# gatedriver_ixys.net
KiCad netlist of a schematic drawn in EAGLE
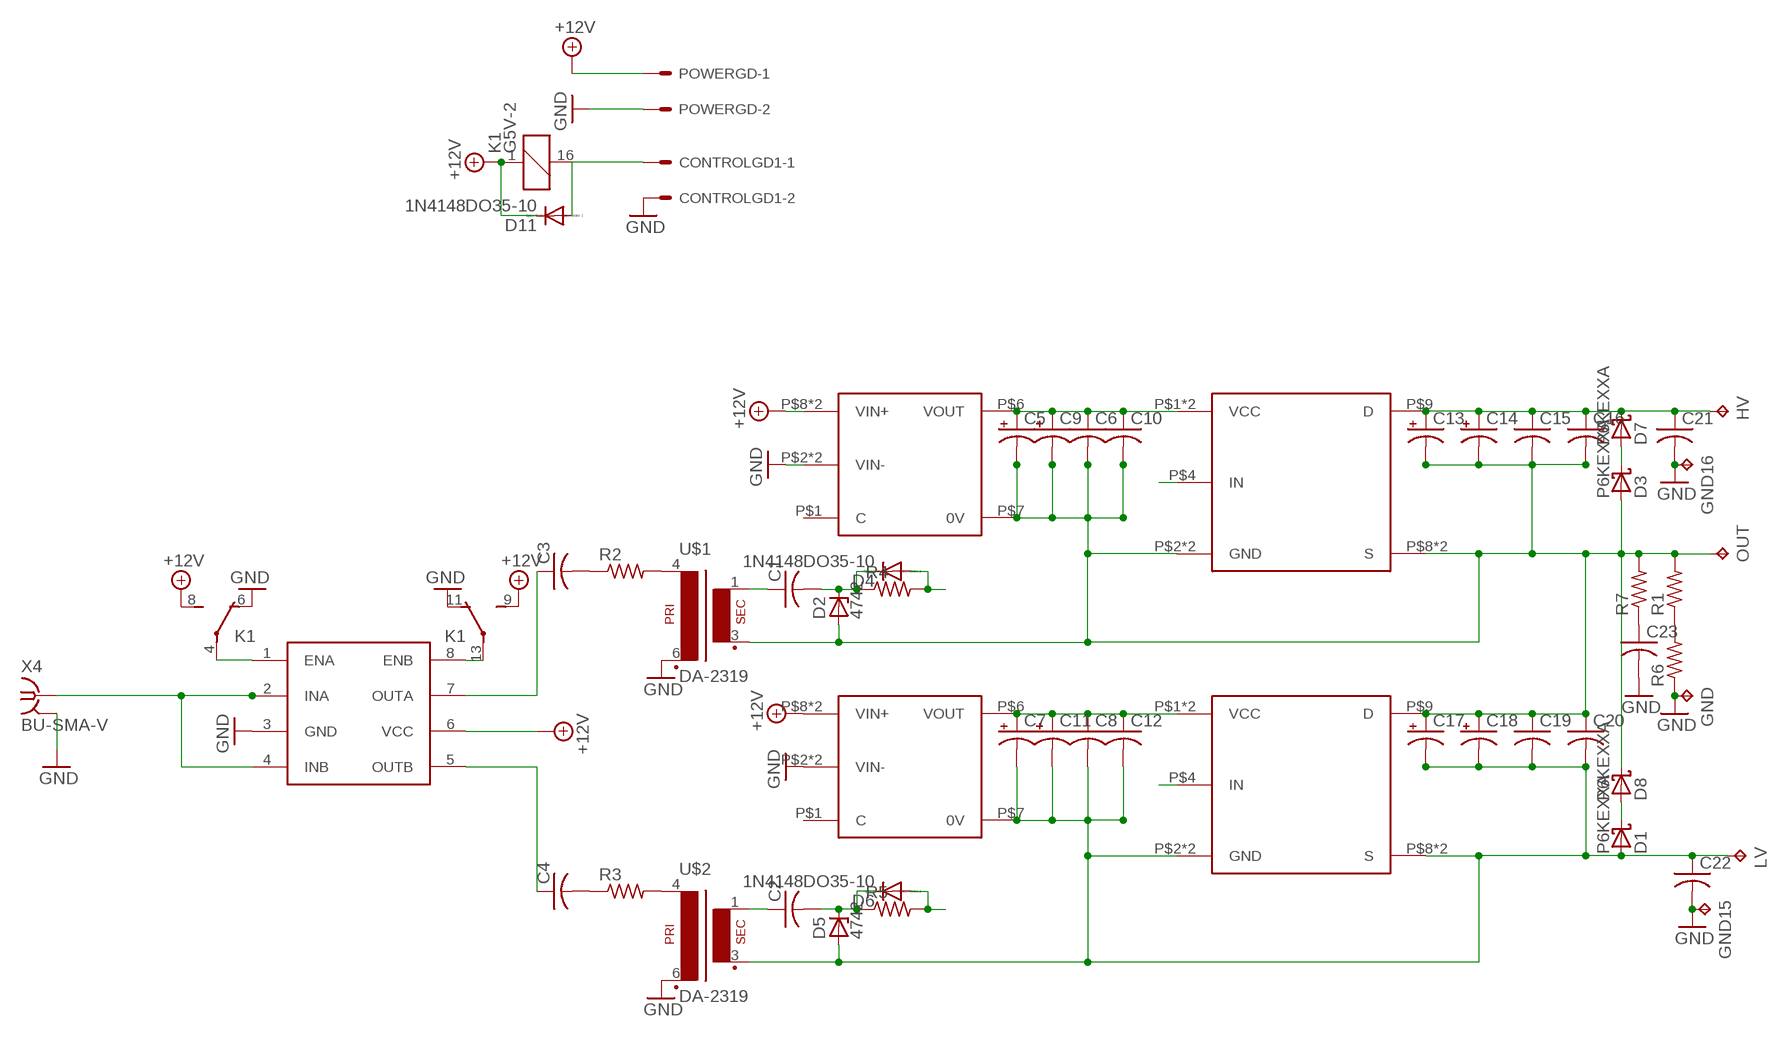
[diagram p0: schematic, sheet 1]

(export (version "E")
  (design (tool "Eeschema 10.0.6"))
  (components
    (comp (ref "C1")
      (value "C-US050-055X075")
      (footprint "eagle-import:C050-055X075")
      (libsource (lib "eagle-import") (part "resistor_C-US050-055X075"))
    )
    (comp (ref "C2")
      (value "C-US050-055X075")
      (footprint "eagle-import:C050-055X075")
      (libsource (lib "eagle-import") (part "resistor_C-US050-055X075"))
    )
    (comp (ref "C3")
      (value "C-US050-055X075")
      (footprint "eagle-import:C050-055X075")
      (libsource (lib "eagle-import") (part "resistor_C-US050-055X075"))
    )
    (comp (ref "C4")
      (value "C-US050-055X075")
      (footprint "eagle-import:C050-055X075")
      (libsource (lib "eagle-import") (part "resistor_C-US050-055X075"))
    )
    (comp (ref "C5")
      (value "CPOL-USE5-10.5")
      (footprint "eagle-import:E5-10,5")
      (libsource (lib "eagle-import") (part "CPOL-USE5-10.5"))
    )
    (comp (ref "C6")
      (value "C-US050-075X075")
      (footprint "eagle-import:C050-075X075")
      (libsource (lib "eagle-import") (part "resistor_C-US050-075X075"))
    )
    (comp (ref "C7")
      (value "CPOL-USE5-10.5")
      (footprint "eagle-import:E5-10,5")
      (libsource (lib "eagle-import") (part "CPOL-USE5-10.5"))
    )
    (comp (ref "C8")
      (value "C-US050-075X075")
      (footprint "eagle-import:C050-075X075")
      (libsource (lib "eagle-import") (part "resistor_C-US050-075X075"))
    )
    (comp (ref "C9")
      (value "CPOL-USE5-10.5")
      (footprint "eagle-import:E5-10,5")
      (libsource (lib "eagle-import") (part "CPOL-USE5-10.5"))
    )
    (comp (ref "C10")
      (value "C-US050-075X075")
      (footprint "eagle-import:C050-075X075")
      (libsource (lib "eagle-import") (part "resistor_C-US050-075X075"))
    )
    (comp (ref "C11")
      (value "CPOL-USE5-10.5")
      (footprint "eagle-import:E5-10,5")
      (libsource (lib "eagle-import") (part "CPOL-USE5-10.5"))
    )
    (comp (ref "C12")
      (value "C-US050-075X075")
      (footprint "eagle-import:C050-075X075")
      (libsource (lib "eagle-import") (part "resistor_C-US050-075X075"))
    )
    (comp (ref "C13")
      (value "CPOL-USE5-10.5")
      (footprint "eagle-import:E5-10,5")
      (libsource (lib "eagle-import") (part "CPOL-USE5-10.5"))
    )
    (comp (ref "C14")
      (value "CPOL-USE5-10.5")
      (footprint "eagle-import:E5-10,5")
      (libsource (lib "eagle-import") (part "CPOL-USE5-10.5"))
    )
    (comp (ref "C15")
      (value "C-US050-075X075")
      (footprint "eagle-import:C050-075X075")
      (libsource (lib "eagle-import") (part "resistor_C-US050-075X075"))
    )
    (comp (ref "C16")
      (value "C-US050-075X075")
      (footprint "eagle-import:C050-075X075")
      (libsource (lib "eagle-import") (part "resistor_C-US050-075X075"))
    )
    (comp (ref "C17")
      (value "CPOL-USE5-10.5")
      (footprint "eagle-import:E5-10,5")
      (libsource (lib "eagle-import") (part "CPOL-USE5-10.5"))
    )
    (comp (ref "C18")
      (value "CPOL-USE5-10.5")
      (footprint "eagle-import:E5-10,5")
      (libsource (lib "eagle-import") (part "CPOL-USE5-10.5"))
    )
    (comp (ref "C19")
      (value "C-US050-075X075")
      (footprint "eagle-import:C050-075X075")
      (libsource (lib "eagle-import") (part "resistor_C-US050-075X075"))
    )
    (comp (ref "C20")
      (value "C-US050-075X075")
      (footprint "eagle-import:C050-075X075")
      (libsource (lib "eagle-import") (part "resistor_C-US050-075X075"))
    )
    (comp (ref "C21")
      (value "C-US102-064X133")
      (footprint "eagle-import:C102-064X133")
      (libsource (lib "eagle-import") (part "C-US102-064X133"))
    )
    (comp (ref "C22")
      (value "C-US102-064X133")
      (footprint "eagle-import:C102-064X133")
      (libsource (lib "eagle-import") (part "C-US102-064X133"))
    )
    (comp (ref "C23")
      (value "C-US102-064X133")
      (footprint "eagle-import:C102-064X133")
      (libsource (lib "eagle-import") (part "C-US102-064X133"))
    )
    (comp (ref "CONTROLGD1")
      (value "KK-156-2")
      (footprint "eagle-import:KK-156-2")
      (libsource (lib "eagle-import") (part "KK-156-2"))
    )
    (comp (ref "D1")
      (value "P6KEXXA")
      (footprint "eagle-import:C1702-15")
      (libsource (lib "eagle-import") (part "P6KEXXA"))
    )
    (comp (ref "D2")
      (value "4742")
      (footprint "eagle-import:ZDIO-10")
      (libsource (lib "eagle-import") (part "ZENER-DIODEZD-10"))
    )
    (comp (ref "D3")
      (value "P6KEXXA")
      (footprint "eagle-import:C1702-15")
      (libsource (lib "eagle-import") (part "P6KEXXA"))
    )
    (comp (ref "D4")
      (value "1N4148DO35-10")
      (footprint "eagle-import:DO35-10")
      (libsource (lib "eagle-import") (part "1N4148DO35-10"))
    )
    (comp (ref "D5")
      (value "4742")
      (footprint "eagle-import:ZDIO-10")
      (libsource (lib "eagle-import") (part "ZENER-DIODEZD-10"))
    )
    (comp (ref "D6")
      (value "1N4148DO35-10")
      (footprint "eagle-import:DO35-10")
      (libsource (lib "eagle-import") (part "1N4148DO35-10"))
    )
    (comp (ref "D7")
      (value "P6KEXXA")
      (footprint "eagle-import:C1702-15")
      (libsource (lib "eagle-import") (part "P6KEXXA"))
    )
    (comp (ref "D8")
      (value "P6KEXXA")
      (footprint "eagle-import:C1702-15")
      (libsource (lib "eagle-import") (part "P6KEXXA"))
    )
    (comp (ref "D11")
      (value "1N4148DO35-10")
      (footprint "eagle-import:DO35-10")
      (libsource (lib "eagle-import") (part "1N4148DO35-10"))
    )
    (comp (ref "DC1")
      (value "NCS")
      (footprint "eagle-import:NCS")
      (libsource (lib "eagle-import") (part "NCS"))
    )
    (comp (ref "DC2")
      (value "NCS")
      (footprint "eagle-import:NCS")
      (libsource (lib "eagle-import") (part "NCS"))
    )
    (comp (ref "GND")
      (value "TPPAD1-20Y")
      (footprint "eagle-import:P1-20Y")
      (libsource (lib "eagle-import") (part "TPPAD1-20Y"))
    )
    (comp (ref "GND15")
      (value "TPPAD1-20Y")
      (footprint "eagle-import:P1-20Y")
      (libsource (lib "eagle-import") (part "TPPAD1-20Y"))
    )
    (comp (ref "GND16")
      (value "TPPAD1-20Y")
      (footprint "eagle-import:P1-20Y")
      (libsource (lib "eagle-import") (part "TPPAD1-20Y"))
    )
    (comp (ref "HV")
      (value "TPPAD1-20Y")
      (footprint "eagle-import:P1-20Y")
      (libsource (lib "eagle-import") (part "TPPAD1-20Y"))
    )
    (comp (ref "K1")
      (value "G5V-2")
      (footprint "eagle-import:G5V-2")
      (fields (field (name "MPN") "G5V-2 5DC"))
      (libsource (lib "eagle-import") (part "G5V-2"))
    )
    (comp (ref "LV")
      (value "TPPAD1-20Y")
      (footprint "eagle-import:P1-20Y")
      (libsource (lib "eagle-import") (part "TPPAD1-20Y"))
    )
    (comp (ref "OUT")
      (value "TPPAD1-20Y")
      (footprint "eagle-import:P1-20Y")
      (libsource (lib "eagle-import") (part "TPPAD1-20Y"))
    )
    (comp (ref "POWERGD")
      (value "KK-156-2")
      (footprint "eagle-import:KK-156-2")
      (libsource (lib "eagle-import") (part "KK-156-2"))
    )
    (comp (ref "R1")
      (value "R-US_0414/15")
      (footprint "eagle-import:0414_15")
      (libsource (lib "eagle-import") (part "R-US_0414/15"))
    )
    (comp (ref "R2")
      (value "R-US_0207/15")
      (footprint "eagle-import:0207_15")
      (libsource (lib "eagle-import") (part "R-US_0207/15"))
    )
    (comp (ref "R3")
      (value "R-US_0207/12")
      (footprint "eagle-import:0207_12")
      (libsource (lib "eagle-import") (part "R-US_0207/12"))
    )
    (comp (ref "R4")
      (value "R-US_0207/10")
      (footprint "eagle-import:0207_10")
      (libsource (lib "eagle-import") (part "R-US_0207/10"))
    )
    (comp (ref "R5")
      (value "R-US_0207/10")
      (footprint "eagle-import:0207_10")
      (libsource (lib "eagle-import") (part "R-US_0207/10"))
    )
    (comp (ref "R6")
      (value "R-US_0414/15")
      (footprint "eagle-import:0414_15")
      (libsource (lib "eagle-import") (part "R-US_0414/15"))
    )
    (comp (ref "R7")
      (value "R-US_0414/15")
      (footprint "eagle-import:0414_15")
      (libsource (lib "eagle-import") (part "R-US_0414/15"))
    )
    (comp (ref "U$1")
      (value "DA-2319")
      (footprint "eagle-import:DIL06")
      (libsource (lib "eagle-import") (part "DA-2319"))
    )
    (comp (ref "U$2")
      (value "DA-2319")
      (footprint "eagle-import:DIL06")
      (libsource (lib "eagle-import") (part "DA-2319"))
    )
    (comp (ref "U$3")
      (value "UCC27425")
      (footprint "eagle-import:DIL08")
      (libsource (lib "eagle-import") (part "UCC27425"))
    )
    (comp (ref "U$8")
      (value "IXZ631DF12N100")
      (footprint "eagle-import:IXZ631DF12N100")
      (libsource (lib "eagle-import") (part "IXZ631DF12N100"))
    )
    (comp (ref "U$9")
      (value "IXZ631DF12N100")
      (footprint "eagle-import:IXZ631DF12N100")
      (libsource (lib "eagle-import") (part "IXZ631DF12N100"))
    )
    (comp (ref "X4")
      (value "BU-SMA-V")
      (footprint "eagle-import:BU-SMA-V")
      (libsource (lib "eagle-import") (part "BU-SMA-V"))
    )
  )
  (nets
    (net (code "1") (name "+12V") (class "Default")
      (node (ref "D11") (pin "C") (pinfunction "C_C") (pintype "passive"))
      (node (ref "DC1") (pin "P$8") (pinfunction "VIN+_P$8") (pintype "bidirectional"))
      (node (ref "DC1") (pin "P$9") (pinfunction "VIN+_P$9") (pintype "bidirectional"))
      (node (ref "DC2") (pin "P$8") (pinfunction "VIN+_P$8") (pintype "bidirectional"))
      (node (ref "DC2") (pin "P$9") (pinfunction "VIN+_P$9") (pintype "bidirectional"))
      (node (ref "K1") (pin "1") (pinfunction "1_1") (pintype "passive"))
      (node (ref "K1") (pin "8") (pinfunction "S_8") (pintype "passive"))
      (node (ref "K1") (pin "9") (pinfunction "S_9") (pintype "passive"))
      (node (ref "POWERGD") (pin "1") (pinfunction "S_1") (pintype "passive"))
      (node (ref "U$3") (pin "6") (pinfunction "VCC_6") (pintype "bidirectional"))
    )
    (net (code "2") (name "/GD_HI") (class "Default")
      (node (ref "D4") (pin "A") (pinfunction "A_A") (pintype "passive"))
      (node (ref "R4") (pin "2") (pinfunction "2_2") (pintype "passive"))
      (node (ref "U$8") (pin "P$4") (pinfunction "IN_P$4") (pintype "bidirectional"))
    )
    (net (code "3") (name "/GD_LO") (class "Default")
      (node (ref "D6") (pin "A") (pinfunction "A_A") (pintype "passive"))
      (node (ref "R5") (pin "2") (pinfunction "2_2") (pintype "passive"))
      (node (ref "U$9") (pin "P$4") (pinfunction "IN_P$4") (pintype "bidirectional"))
    )
    (net (code "4") (name "GND") (class "Default")
      (node (ref "C21") (pin "2") (pinfunction "2_2") (pintype "passive"))
      (node (ref "C22") (pin "2") (pinfunction "2_2") (pintype "passive"))
      (node (ref "C23") (pin "2") (pinfunction "2_2") (pintype "passive"))
      (node (ref "CONTROLGD1") (pin "2") (pinfunction "S_2") (pintype "passive"))
      (node (ref "DC1") (pin "P$2") (pinfunction "VIN-_P$2") (pintype "bidirectional"))
      (node (ref "DC1") (pin "P$3") (pinfunction "VIN-_P$3") (pintype "bidirectional"))
      (node (ref "DC2") (pin "P$2") (pinfunction "VIN-_P$2") (pintype "bidirectional"))
      (node (ref "DC2") (pin "P$3") (pinfunction "VIN-_P$3") (pintype "bidirectional"))
      (node (ref "GND") (pin "TP") (pinfunction "TP_TP") (pintype "input"))
      (node (ref "GND15") (pin "TP") (pinfunction "TP_TP") (pintype "input"))
      (node (ref "GND16") (pin "TP") (pinfunction "TP_TP") (pintype "input"))
      (node (ref "K1") (pin "11") (pinfunction "O_11") (pintype "passive"))
      (node (ref "K1") (pin "6") (pinfunction "O_6") (pintype "passive"))
      (node (ref "POWERGD") (pin "2") (pinfunction "S_2") (pintype "passive"))
      (node (ref "R6") (pin "1") (pinfunction "1_1") (pintype "passive"))
      (node (ref "U$1") (pin "6") (pinfunction "P2_6") (pintype "passive"))
      (node (ref "U$2") (pin "6") (pinfunction "P2_6") (pintype "passive"))
      (node (ref "U$3") (pin "3") (pinfunction "GND_3") (pintype "bidirectional"))
      (node (ref "X4") (pin "2") (pinfunction "2_2") (pintype "passive"))
      (node (ref "X4") (pin "3") (pinfunction "2_3") (pintype "passive"))
      (node (ref "X4") (pin "4") (pinfunction "2_4") (pintype "passive"))
      (node (ref "X4") (pin "5") (pinfunction "2_5") (pintype "passive"))
    )
    (net (code "5") (name "Net-(C1-Pad2)") (class "Default")
      (node (ref "C1") (pin "2") (pinfunction "2_2") (pintype "passive"))
      (node (ref "D2") (pin "C") (pinfunction "C_C") (pintype "passive"))
      (node (ref "D4") (pin "C") (pinfunction "C_C") (pintype "passive"))
      (node (ref "R4") (pin "1") (pinfunction "1_1") (pintype "passive"))
    )
    (net (code "6") (name "Net-(C2-Pad2)") (class "Default")
      (node (ref "C2") (pin "2") (pinfunction "2_2") (pintype "passive"))
      (node (ref "D5") (pin "C") (pinfunction "C_C") (pintype "passive"))
      (node (ref "D6") (pin "C") (pinfunction "C_C") (pintype "passive"))
      (node (ref "R5") (pin "1") (pinfunction "1_1") (pintype "passive"))
    )
    (net (code "7") (name "Net-(C3-Pad2)") (class "Default")
      (node (ref "C3") (pin "2") (pinfunction "2_2") (pintype "passive"))
      (node (ref "R2") (pin "1") (pinfunction "1_1") (pintype "passive"))
    )
    (net (code "8") (name "Net-(C4-Pad2)") (class "Default")
      (node (ref "C4") (pin "2") (pinfunction "2_2") (pintype "passive"))
      (node (ref "R3") (pin "1") (pinfunction "1_1") (pintype "passive"))
    )
    (net (code "9") (name "Net-(C23-Pad1)") (class "Default")
      (node (ref "C23") (pin "1") (pinfunction "1_1") (pintype "passive"))
      (node (ref "R7") (pin "1") (pinfunction "1_1") (pintype "passive"))
    )
    (net (code "10") (name "Net-(CONTROLGD1A-S)") (class "Default")
      (node (ref "CONTROLGD1") (pin "1") (pinfunction "S_1") (pintype "passive"))
      (node (ref "D11") (pin "A") (pinfunction "A_A") (pintype "passive"))
      (node (ref "K1") (pin "16") (pinfunction "2_16") (pintype "passive"))
    )
    (net (code "11") (name "Net-(D1-PadC)") (class "Default")
      (node (ref "D1") (pin "C") (pinfunction "C_C") (pintype "passive"))
      (node (ref "D8") (pin "A") (pinfunction "A_A") (pintype "passive"))
    )
    (net (code "12") (name "Net-(D3-PadC)") (class "Default")
      (node (ref "D3") (pin "C") (pinfunction "C_C") (pintype "passive"))
      (node (ref "D7") (pin "A") (pinfunction "A_A") (pintype "passive"))
    )
    (net (code "13") (name "Net-(DC1-0V)") (class "Default")
      (node (ref "C10") (pin "2") (pinfunction "2_2") (pintype "passive"))
      (node (ref "C13") (pin "-") (pinfunction "-_-") (pintype "passive"))
      (node (ref "C14") (pin "-") (pinfunction "-_-") (pintype "passive"))
      (node (ref "C15") (pin "2") (pinfunction "2_2") (pintype "passive"))
      (node (ref "C16") (pin "2") (pinfunction "2_2") (pintype "passive"))
      (node (ref "C17") (pin "+") (pinfunction "+_+") (pintype "passive"))
      (node (ref "C18") (pin "+") (pinfunction "+_+") (pintype "passive"))
      (node (ref "C19") (pin "1") (pinfunction "1_1") (pintype "passive"))
      (node (ref "C20") (pin "1") (pinfunction "1_1") (pintype "passive"))
      (node (ref "C5") (pin "-") (pinfunction "-_-") (pintype "passive"))
      (node (ref "C6") (pin "2") (pinfunction "2_2") (pintype "passive"))
      (node (ref "C9") (pin "-") (pinfunction "-_-") (pintype "passive"))
      (node (ref "D2") (pin "A") (pinfunction "A_A") (pintype "passive"))
      (node (ref "D3") (pin "A") (pinfunction "A_A") (pintype "passive"))
      (node (ref "D8") (pin "C") (pinfunction "C_C") (pintype "passive"))
      (node (ref "DC1") (pin "P$7") (pinfunction "0V_P$7") (pintype "bidirectional"))
      (node (ref "OUT") (pin "TP") (pinfunction "TP_TP") (pintype "input"))
      (node (ref "R1") (pin "2") (pinfunction "2_2") (pintype "passive"))
      (node (ref "R7") (pin "2") (pinfunction "2_2") (pintype "passive"))
      (node (ref "U$1") (pin "3") (pinfunction "S3_3") (pintype "passive"))
      (node (ref "U$8") (pin "P$10") (pinfunction "S_P$10") (pintype "bidirectional"))
      (node (ref "U$8") (pin "P$2") (pinfunction "GND_P$2") (pintype "bidirectional"))
      (node (ref "U$8") (pin "P$6") (pinfunction "GND_P$6") (pintype "bidirectional"))
      (node (ref "U$8") (pin "P$8") (pinfunction "S_P$8") (pintype "bidirectional"))
      (node (ref "U$9") (pin "P$9") (pinfunction "D_P$9") (pintype "bidirectional"))
    )
    (net (code "14") (name "Net-(DC1-VOUT)") (class "Default")
      (node (ref "C10") (pin "1") (pinfunction "1_1") (pintype "passive"))
      (node (ref "C5") (pin "+") (pinfunction "+_+") (pintype "passive"))
      (node (ref "C6") (pin "1") (pinfunction "1_1") (pintype "passive"))
      (node (ref "C9") (pin "+") (pinfunction "+_+") (pintype "passive"))
      (node (ref "DC1") (pin "P$6") (pinfunction "VOUT_P$6") (pintype "bidirectional"))
      (node (ref "U$8") (pin "P$1") (pinfunction "VCC_P$1") (pintype "bidirectional"))
      (node (ref "U$8") (pin "P$7") (pinfunction "VCC_P$7") (pintype "bidirectional"))
    )
    (net (code "15") (name "Net-(DC2-0V)") (class "Default")
      (node (ref "C11") (pin "-") (pinfunction "-_-") (pintype "passive"))
      (node (ref "C12") (pin "2") (pinfunction "2_2") (pintype "passive"))
      (node (ref "C17") (pin "-") (pinfunction "-_-") (pintype "passive"))
      (node (ref "C18") (pin "-") (pinfunction "-_-") (pintype "passive"))
      (node (ref "C19") (pin "2") (pinfunction "2_2") (pintype "passive"))
      (node (ref "C20") (pin "2") (pinfunction "2_2") (pintype "passive"))
      (node (ref "C22") (pin "1") (pinfunction "1_1") (pintype "passive"))
      (node (ref "C7") (pin "-") (pinfunction "-_-") (pintype "passive"))
      (node (ref "C8") (pin "2") (pinfunction "2_2") (pintype "passive"))
      (node (ref "D1") (pin "A") (pinfunction "A_A") (pintype "passive"))
      (node (ref "D5") (pin "A") (pinfunction "A_A") (pintype "passive"))
      (node (ref "DC2") (pin "P$7") (pinfunction "0V_P$7") (pintype "bidirectional"))
      (node (ref "LV") (pin "TP") (pinfunction "TP_TP") (pintype "input"))
      (node (ref "U$2") (pin "3") (pinfunction "S3_3") (pintype "passive"))
      (node (ref "U$9") (pin "P$10") (pinfunction "S_P$10") (pintype "bidirectional"))
      (node (ref "U$9") (pin "P$2") (pinfunction "GND_P$2") (pintype "bidirectional"))
      (node (ref "U$9") (pin "P$6") (pinfunction "GND_P$6") (pintype "bidirectional"))
      (node (ref "U$9") (pin "P$8") (pinfunction "S_P$8") (pintype "bidirectional"))
    )
    (net (code "16") (name "Net-(DC2-VOUT)") (class "Default")
      (node (ref "C11") (pin "+") (pinfunction "+_+") (pintype "passive"))
      (node (ref "C12") (pin "1") (pinfunction "1_1") (pintype "passive"))
      (node (ref "C7") (pin "+") (pinfunction "+_+") (pintype "passive"))
      (node (ref "C8") (pin "1") (pinfunction "1_1") (pintype "passive"))
      (node (ref "DC2") (pin "P$6") (pinfunction "VOUT_P$6") (pintype "bidirectional"))
      (node (ref "U$9") (pin "P$1") (pinfunction "VCC_P$1") (pintype "bidirectional"))
      (node (ref "U$9") (pin "P$7") (pinfunction "VCC_P$7") (pintype "bidirectional"))
    )
    (net (code "17") (name "Net-(K1A-P)") (class "Default")
      (node (ref "K1") (pin "4") (pinfunction "P_4") (pintype "passive"))
      (node (ref "U$3") (pin "1") (pinfunction "ENA_1") (pintype "bidirectional"))
    )
    (net (code "18") (name "Net-(K1B-P)") (class "Default")
      (node (ref "K1") (pin "13") (pinfunction "P_13") (pintype "passive"))
      (node (ref "U$3") (pin "8") (pinfunction "ENB_8") (pintype "bidirectional"))
    )
    (net (code "19") (name "Net-(R1-Pad1)") (class "Default")
      (node (ref "R1") (pin "1") (pinfunction "1_1") (pintype "passive"))
      (node (ref "R6") (pin "2") (pinfunction "2_2") (pintype "passive"))
    )
    (net (code "20") (name "Net-(U$1-P1)") (class "Default")
      (node (ref "R2") (pin "2") (pinfunction "2_2") (pintype "passive"))
      (node (ref "U$1") (pin "4") (pinfunction "P1_4") (pintype "passive"))
    )
    (net (code "21") (name "Net-(U$1-S4)") (class "Default")
      (node (ref "C1") (pin "1") (pinfunction "1_1") (pintype "passive"))
      (node (ref "U$1") (pin "1") (pinfunction "S4_1") (pintype "passive"))
    )
    (net (code "22") (name "Net-(U$2-P1)") (class "Default")
      (node (ref "R3") (pin "2") (pinfunction "2_2") (pintype "passive"))
      (node (ref "U$2") (pin "4") (pinfunction "P1_4") (pintype "passive"))
    )
    (net (code "23") (name "Net-(U$2-S4)") (class "Default")
      (node (ref "C2") (pin "1") (pinfunction "1_1") (pintype "passive"))
      (node (ref "U$2") (pin "1") (pinfunction "S4_1") (pintype "passive"))
    )
    (net (code "24") (name "Net-(U$3-INA)") (class "Default")
      (node (ref "U$3") (pin "2") (pinfunction "INA_2") (pintype "bidirectional"))
      (node (ref "U$3") (pin "4") (pinfunction "INB_4") (pintype "bidirectional"))
      (node (ref "X4") (pin "1") (pinfunction "1_1") (pintype "passive"))
    )
    (net (code "25") (name "Net-(U$3-OUTA)") (class "Default")
      (node (ref "C3") (pin "1") (pinfunction "1_1") (pintype "passive"))
      (node (ref "U$3") (pin "7") (pinfunction "OUTA_7") (pintype "bidirectional"))
    )
    (net (code "26") (name "Net-(U$3-OUTB)") (class "Default")
      (node (ref "C4") (pin "1") (pinfunction "1_1") (pintype "passive"))
      (node (ref "U$3") (pin "5") (pinfunction "OUTB_5") (pintype "bidirectional"))
    )
    (net (code "27") (name "Net-(U$8-D)") (class "Default")
      (node (ref "C13") (pin "+") (pinfunction "+_+") (pintype "passive"))
      (node (ref "C14") (pin "+") (pinfunction "+_+") (pintype "passive"))
      (node (ref "C15") (pin "1") (pinfunction "1_1") (pintype "passive"))
      (node (ref "C16") (pin "1") (pinfunction "1_1") (pintype "passive"))
      (node (ref "C21") (pin "1") (pinfunction "1_1") (pintype "passive"))
      (node (ref "D7") (pin "C") (pinfunction "C_C") (pintype "passive"))
      (node (ref "HV") (pin "TP") (pinfunction "TP_TP") (pintype "input"))
      (node (ref "U$8") (pin "P$9") (pinfunction "D_P$9") (pintype "bidirectional"))
    )
    (net (code "28") (name "unconnected-(DC1-C-PadP$1)") (class "Default")
      (node (ref "DC1") (pin "P$1") (pinfunction "C_P$1") (pintype "bidirectional"))
    )
    (net (code "29") (name "unconnected-(DC2-C-PadP$1)") (class "Default")
      (node (ref "DC2") (pin "P$1") (pinfunction "C_P$1") (pintype "bidirectional"))
    )
  )
)
